# H0DR9_Backend.net
KiCad netlist of a schematic drawn in Altium Designer
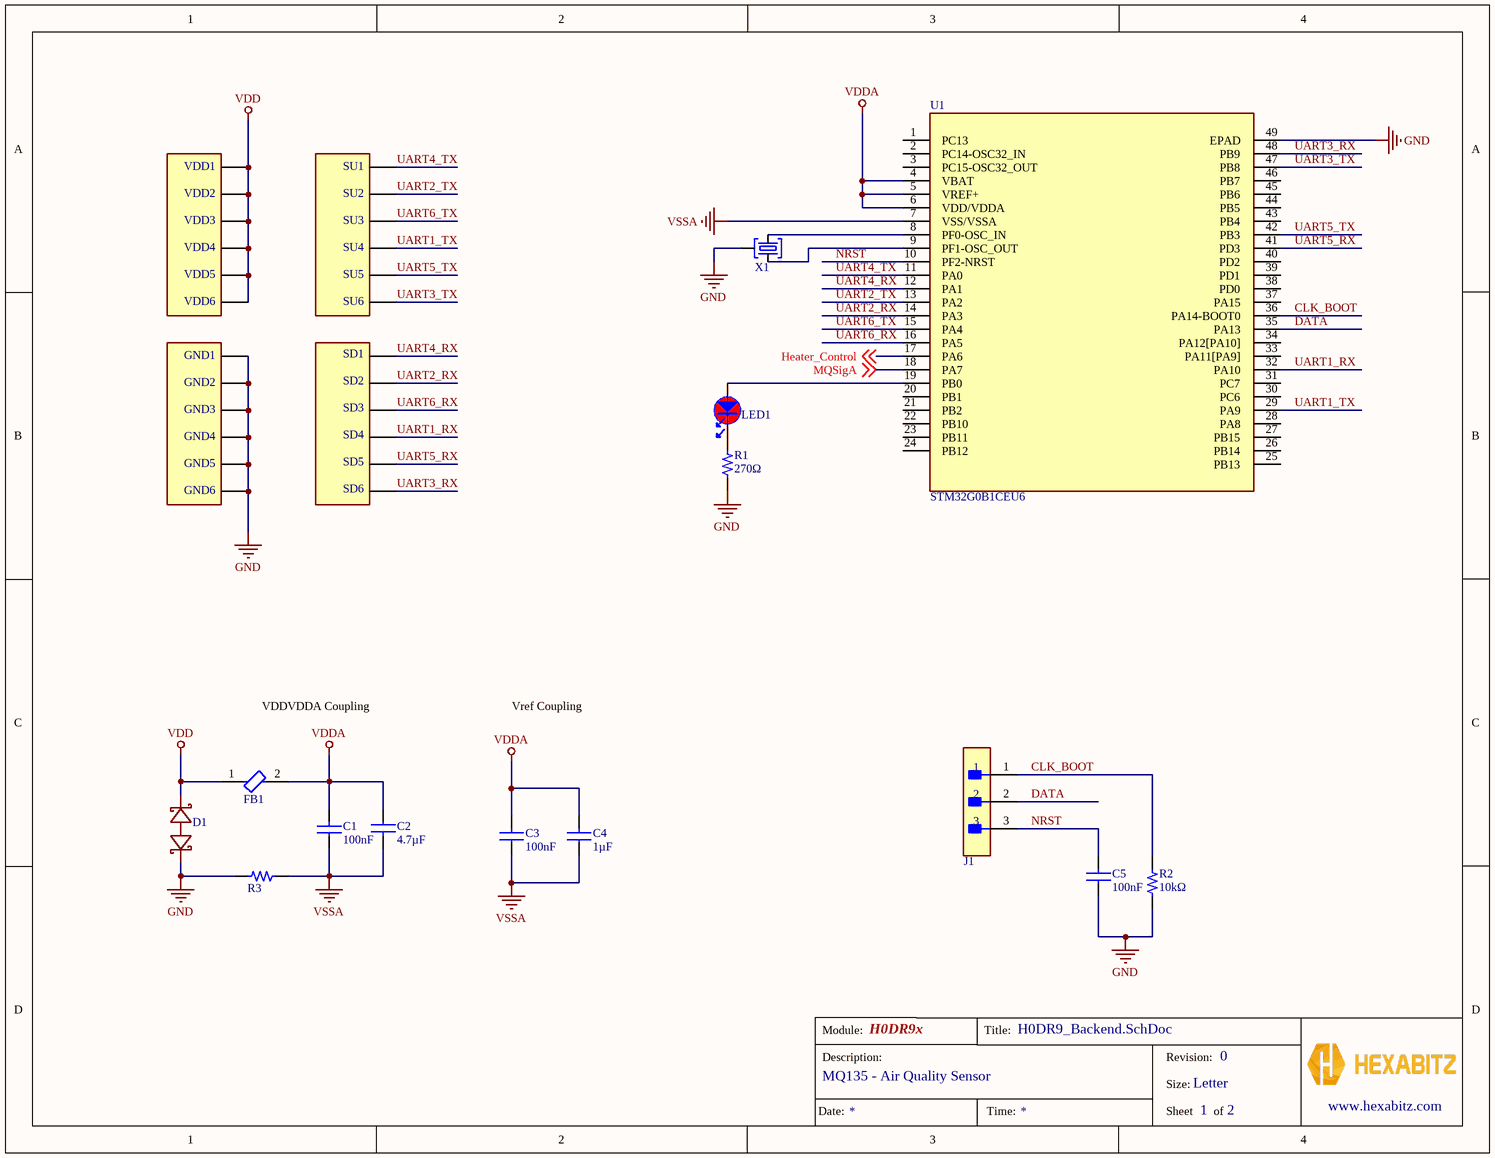
[diagram p0: H0DR9_Backend.SchDoc]

(export (version "E")
  (design (tool "Eeschema 10.0.6"))
  (components
    (comp (ref "C1")
      (value "100nF")
      (footprint "C0603")
      (fields
        (field (name "MANUFACTURER") "Samsung Electro-Mechanics")
        (field (name "MANUFACTURER PART NUMBER") "CL10B104KA8NNNC")
        (field (name "TOLERANCE") "10%")
      )
      (libsource (lib "Hexabitz Altium Library") (part "generic Capacitor"))
    )
    (comp (ref "C2")
      (value "4.7µF")
      (footprint "C0805")
      (fields
        (field (name "MANUFACTURER") "Samsung Electro-Mechanics")
        (field (name "MANUFACTURER PART NUMBER") "CL21X475KAQNNNE")
        (field (name "TOLERANCE") "10%")
      )
      (libsource (lib "Hexabitz Altium Library") (part "generic Capacitor"))
    )
    (comp (ref "C3")
      (value "100nF")
      (footprint "C0603")
      (fields
        (field (name "MANUFACTURER") "Samsung Electro-Mechanics")
        (field (name "MANUFACTURER PART NUMBER") "CL10B104KA8NNNC")
        (field (name "TOLERANCE") "10%")
      )
      (libsource (lib "Hexabitz Altium Library") (part "generic Capacitor"))
    )
    (comp (ref "C4")
      (value "1µF")
      (footprint "C0805")
      (description "Ceramic Capacitor, Ceramic, 16V, 10% +Tol, 10% -Tol, X7R, 15% TC, 1uF, Surface Mount, 0805")
      (fields
        (field (name "MANUFACTURER") "Yageo Group")
        (field (name "MANUFACTURER PART NUMBER") "CC0805KKX7R7BB105")
      )
      (libsource (lib "Hexabitz Altium Library") (part "generic Capacitor"))
    )
    (comp (ref "C5")
      (value "100nF")
      (footprint "C0603")
      (fields
        (field (name "MANUFACTURER") "Samsung Electro-Mechanics")
        (field (name "MANUFACTURER PART NUMBER") "CL10B104KA8NNNC")
        (field (name "TOLERANCE") "10%")
      )
      (libsource (lib "Hexabitz Altium Library") (part "generic Capacitor"))
    )
    (comp (ref "D1")
      (value "CDSOD323-T03SC")
      (footprint "SOD2513X114N")
      (description "A 3V, 350W, bi-directional, standard capacitance, SOD323 pkg TVS Diode ¦ Bourns CDSOD323-T03SC")
      (fields (field (name "MANUFACTURER") "Bourns"))
      (libsource (lib "Hexabitz Altium Library") (part "CDSOD323-T03SC"))
    )
    (comp (ref "FB1")
      (value "MMZ1608Y300B")
      (footprint "FP-MMZ1608-0_8-MFG")
      (description "Ferrite Beads 0603 30ohms 1500mA Signal Line AEC-Q200")
      (fields
        (field (name "MANUFACTURER") "TDK")
        (field (name "MANUFACTURER PART NUMBER") "MMZ1608Y300BTD25")
      )
      (libsource (lib "Hexabitz Altium Library") (part "MMZ1608Y300B"))
    )
    (comp (ref "GND1")
      (value "HEXABIT_UART_PORT")
      (footprint "HEXABIT_POWER_PORT_D")
      (libsource (lib "hexabitz_connectors.Library") (part "HEXABIT_POWER_PORT_D"))
    )
    (comp (ref "GND2")
      (value "HEXABIT_UART_PORT")
      (footprint "HEXABIT_POWER_PORT_D")
      (libsource (lib "hexabitz_connectors.Library") (part "HEXABIT_POWER_PORT_D"))
    )
    (comp (ref "GND3")
      (value "HEXABIT_UART_PORT")
      (footprint "HEXABIT_POWER_PORT_D")
      (libsource (lib "hexabitz_connectors.Library") (part "HEXABIT_POWER_PORT_D"))
    )
    (comp (ref "GND4")
      (value "HEXABIT_UART_PORT")
      (footprint "HEXABIT_POWER_PORT_D")
      (libsource (lib "hexabitz_connectors.Library") (part "HEXABIT_POWER_PORT_D"))
    )
    (comp (ref "GND5")
      (value "HEXABIT_UART_PORT")
      (footprint "HEXABIT_POWER_PORT_D")
      (libsource (lib "hexabitz_connectors.Library") (part "HEXABIT_POWER_PORT_D"))
    )
    (comp (ref "GND6")
      (value "HEXABIT_UART_PORT")
      (footprint "HEXABIT_POWER_PORT_D")
      (libsource (lib "hexabitz_connectors.Library") (part "HEXABIT_POWER_PORT_D"))
    )
    (comp (ref "J1")
      (value "TSW-103-14-G-S")
      (footprint "FP-TSW-103-14-G-S-MFG")
      (description "CONN HEADER VERT 3POS 2.54MM")
      (libsource (lib "Altium Content Vault") (part "cd3439d6ef35ae5d9b27ec4fdd3e828"))
    )
    (comp (ref "LED1")
      (value "VLMS1300-GS08")
      (footprint "FP-6_541-5092_01-4-MFG")
      (description "LED Uni-Color Super Red 639nm 2-Pin Chip 0603(1608Metric) T/R")
      (fields (field (name "MANUFACTURER") "Vishay Semiconductors"))
      (libsource (lib "Hexabitz Altium Library") (part "VLMS1300-GS08"))
    )
    (comp (ref "R1")
      (value "270Ω")
      (footprint "R0603")
      (description "Res Thick Film 0603 270 Ohm 5% 0.1W(1/10W) ±200ppm/C Pad SMD Automotive T/R")
      (fields
        (field (name "MANUFACTURER") "Panasonic")
        (field (name "MANUFACTURER PART NUMBER") "ERJ-3GEYJ271V")
      )
      (libsource (lib "") (part "generic Resistor_1"))
    )
    (comp (ref "R2")
      (value "10kΩ")
      (footprint "R0603")
      (description "100mW Thick Film Resistors ±100ppm/℃ ±1% 10kΩ 0603 Chip Resistor - Surface Mount ROHS")
      (fields
        (field (name "MANUFACTURER") "Yageo Group")
        (field (name "MANUFACTURER PART NUMBER") "RC0603FR-0710KL")
      )
      (libsource (lib "Hexabitz Altium Library") (part "generic Resistor"))
    )
    (comp (ref "R3")
      (value "Manufacturer Part Number")
      (footprint "R0603")
      (libsource (lib "") (part "generic Resistor_2"))
    )
    (comp (ref "SD1")
      (value "HEXABIT_UART_PORT")
      (footprint "HEXABIT_UART_PORT_D")
      (libsource (lib "hexabitz_connectors.Library") (part "HEXABIT_UART_PORT_D"))
    )
    (comp (ref "SD2")
      (value "HEXABIT_UART_PORT")
      (footprint "HEXABIT_UART_PORT_D")
      (libsource (lib "hexabitz_connectors.Library") (part "HEXABIT_UART_PORT_D"))
    )
    (comp (ref "SD3")
      (value "HEXABIT_UART_PORT")
      (footprint "HEXABIT_UART_PORT_D")
      (libsource (lib "hexabitz_connectors.Library") (part "HEXABIT_UART_PORT_D"))
    )
    (comp (ref "SD4")
      (value "HEXABIT_UART_PORT")
      (footprint "HEXABIT_UART_PORT_D")
      (libsource (lib "hexabitz_connectors.Library") (part "HEXABIT_UART_PORT_D"))
    )
    (comp (ref "SD5")
      (value "HEXABIT_UART_PORT")
      (footprint "HEXABIT_UART_PORT_D")
      (libsource (lib "hexabitz_connectors.Library") (part "HEXABIT_UART_PORT_D"))
    )
    (comp (ref "SD6")
      (value "HEXABIT_UART_PORT")
      (footprint "HEXABIT_UART_PORT_D")
      (libsource (lib "hexabitz_connectors.Library") (part "HEXABIT_UART_PORT_D"))
    )
    (comp (ref "SU1")
      (value "HEXABIT_UART_PORT")
      (footprint "HEXABIT_UART_PORT_U")
      (libsource (lib "hexabitz_connectors.Library") (part "HEXABIT_UART_PORT_U"))
    )
    (comp (ref "SU2")
      (value "HEXABIT_UART_PORT")
      (footprint "HEXABIT_UART_PORT_U")
      (libsource (lib "hexabitz_connectors.Library") (part "HEXABIT_UART_PORT_U"))
    )
    (comp (ref "SU3")
      (value "HEXABIT_UART_PORT")
      (footprint "HEXABIT_UART_PORT_U")
      (libsource (lib "hexabitz_connectors.Library") (part "HEXABIT_UART_PORT_U"))
    )
    (comp (ref "SU4")
      (value "HEXABIT_UART_PORT")
      (footprint "HEXABIT_UART_PORT_U")
      (libsource (lib "hexabitz_connectors.Library") (part "HEXABIT_UART_PORT_U"))
    )
    (comp (ref "SU5")
      (value "HEXABIT_UART_PORT")
      (footprint "HEXABIT_UART_PORT_U")
      (libsource (lib "hexabitz_connectors.Library") (part "HEXABIT_UART_PORT_U"))
    )
    (comp (ref "SU6")
      (value "HEXABIT_UART_PORT")
      (footprint "HEXABIT_UART_PORT_U")
      (libsource (lib "hexabitz_connectors.Library") (part "HEXABIT_UART_PORT_U"))
    )
    (comp (ref "U1")
      (value "STM32G0B1CEU6")
      (footprint "QFN50P700X700X65-49N-D")
      (description "MCU 32-bit ARM Cortex M0+ RISC 512KB Flash 1.8V/2.5V/3.3V 48-Pin UFQFPN EP Tray")
      (fields
        (field (name "MANUFACTURER") "STMicroelectronics")
        (field (name "MANUFACTURER PART NUMBER") "STM32G0B1CEU6")
      )
      (libsource (lib "Hexabitz Altium Library") (part "STM32G0B1CEU6"))
    )
    (comp (ref "VDD1")
      (value "HEXABIT_UART_PORT")
      (footprint "HEXABIT_POWER_PORT_U")
      (libsource (lib "hexabitz_connectors.Library") (part "HEXABIT_POWER_PORT_U"))
    )
    (comp (ref "VDD2")
      (value "HEXABIT_UART_PORT")
      (footprint "HEXABIT_POWER_PORT_U")
      (libsource (lib "hexabitz_connectors.Library") (part "HEXABIT_POWER_PORT_U"))
    )
    (comp (ref "VDD3")
      (value "HEXABIT_UART_PORT")
      (footprint "HEXABIT_POWER_PORT_U")
      (libsource (lib "hexabitz_connectors.Library") (part "HEXABIT_POWER_PORT_U"))
    )
    (comp (ref "VDD4")
      (value "HEXABIT_UART_PORT")
      (footprint "HEXABIT_POWER_PORT_U")
      (libsource (lib "hexabitz_connectors.Library") (part "HEXABIT_POWER_PORT_U"))
    )
    (comp (ref "VDD5")
      (value "HEXABIT_UART_PORT")
      (footprint "HEXABIT_POWER_PORT_U")
      (libsource (lib "hexabitz_connectors.Library") (part "HEXABIT_POWER_PORT_U"))
    )
    (comp (ref "VDD6")
      (value "HEXABIT_UART_PORT")
      (footprint "HEXABIT_POWER_PORT_U")
      (libsource (lib "hexabitz_connectors.Library") (part "HEXABIT_POWER_PORT_U"))
    )
    (comp (ref "X1")
      (value "CSTCE8M00G52Z-R0")
      (footprint "XTALL_CSTCE8M00G52")
      (description "Ceramic Resonator 8MHz ±0.5% (Tol) ±0.2% (Stability) 10pF 40Ohm 3-Pin CSMD T/R")
      (fields (field (name "MANUFACTURER") "Murata") (field (name "TOLERANCE") "0.5%"))
      (libsource (lib "Hexabitz Altium Library") (part "CSTCE8M00G52Z-R0"))
    )
  )
  (nets
    (net (code "1") (name "/CLK_BOOT") (class "Default")
      (node (ref "J1") (pin "1") (pinfunction "1_1") (pintype "passive"))
      (node (ref "R2") (pin "1") (pinfunction "1_1") (pintype "passive"))
      (node (ref "U1") (pin "36") (pinfunction "PA14-BOOT0_36") (pintype "passive"))
    )
    (net (code "2") (name "/DATA") (class "Default")
      (node (ref "J1") (pin "2") (pinfunction "2_2") (pintype "passive"))
      (node (ref "U1") (pin "35") (pinfunction "PA13_35") (pintype "passive"))
    )
    (net (code "3") (name "/NRST") (class "Default")
      (node (ref "C5") (pin "2") (pinfunction "2_2") (pintype "passive"))
      (node (ref "J1") (pin "3") (pinfunction "3_3") (pintype "passive"))
      (node (ref "U1") (pin "10") (pinfunction "PF2-NRST_10") (pintype "passive"))
    )
    (net (code "4") (name "/UART1_RX") (class "Default")
      (node (ref "SD4") (pin "UART_D") (pinfunction "UART_D_UART_D") (pintype "passive"))
      (node (ref "U1") (pin "32") (pinfunction "PA10_32") (pintype "passive"))
    )
    (net (code "5") (name "/UART1_TX") (class "Default")
      (node (ref "SU4") (pin "UART_U") (pinfunction "UART_U_UART_U") (pintype "passive"))
      (node (ref "U1") (pin "29") (pinfunction "PA9_29") (pintype "passive"))
    )
    (net (code "6") (name "/UART2_RX") (class "Default")
      (node (ref "SD2") (pin "UART_D") (pinfunction "UART_D_UART_D") (pintype "passive"))
      (node (ref "U1") (pin "14") (pinfunction "PA3_14") (pintype "passive"))
    )
    (net (code "7") (name "/UART2_TX") (class "Default")
      (node (ref "SU2") (pin "UART_U") (pinfunction "UART_U_UART_U") (pintype "passive"))
      (node (ref "U1") (pin "13") (pinfunction "PA2_13") (pintype "passive"))
    )
    (net (code "8") (name "/UART3_RX") (class "Default")
      (node (ref "SD6") (pin "UART_D") (pinfunction "UART_D_UART_D") (pintype "passive"))
      (node (ref "U1") (pin "48") (pinfunction "PB9_48") (pintype "passive"))
    )
    (net (code "9") (name "/UART3_TX") (class "Default")
      (node (ref "SU6") (pin "UART_U") (pinfunction "UART_U_UART_U") (pintype "passive"))
      (node (ref "U1") (pin "47") (pinfunction "PB8_47") (pintype "passive"))
    )
    (net (code "10") (name "/UART4_RX") (class "Default")
      (node (ref "SD1") (pin "UART_D") (pinfunction "UART_D_UART_D") (pintype "passive"))
      (node (ref "U1") (pin "12") (pinfunction "PA1_12") (pintype "passive"))
    )
    (net (code "11") (name "/UART4_TX") (class "Default")
      (node (ref "SU1") (pin "UART_U") (pinfunction "UART_U_UART_U") (pintype "passive"))
      (node (ref "U1") (pin "11") (pinfunction "PA0_11") (pintype "passive"))
    )
    (net (code "12") (name "/UART5_RX") (class "Default")
      (node (ref "SD5") (pin "UART_D") (pinfunction "UART_D_UART_D") (pintype "passive"))
      (node (ref "U1") (pin "41") (pinfunction "PD3_41") (pintype "passive"))
    )
    (net (code "13") (name "/UART5_TX") (class "Default")
      (node (ref "SU5") (pin "UART_U") (pinfunction "UART_U_UART_U") (pintype "passive"))
      (node (ref "U1") (pin "42") (pinfunction "PB3_42") (pintype "passive"))
    )
    (net (code "14") (name "/UART6_RX") (class "Default")
      (node (ref "SD3") (pin "UART_D") (pinfunction "UART_D_UART_D") (pintype "passive"))
      (node (ref "U1") (pin "16") (pinfunction "PA5_16") (pintype "passive"))
    )
    (net (code "15") (name "/UART6_TX") (class "Default")
      (node (ref "SU3") (pin "UART_U") (pinfunction "UART_U_UART_U") (pintype "passive"))
      (node (ref "U1") (pin "15") (pinfunction "PA4_15") (pintype "passive"))
    )
    (net (code "16") (name "GND") (class "Default")
      (node (ref "C5") (pin "1") (pinfunction "1_1") (pintype "passive"))
      (node (ref "D1") (pin "1") (pinfunction "A_1") (pintype "passive"))
      (node (ref "GND1") (pin "Pwr_D") (pinfunction "Pwr_D_Pwr_D") (pintype "passive"))
      (node (ref "GND2") (pin "Pwr_D") (pinfunction "Pwr_D_Pwr_D") (pintype "passive"))
      (node (ref "GND3") (pin "Pwr_D") (pinfunction "Pwr_D_Pwr_D") (pintype "passive"))
      (node (ref "GND4") (pin "Pwr_D") (pinfunction "Pwr_D_Pwr_D") (pintype "passive"))
      (node (ref "GND5") (pin "Pwr_D") (pinfunction "Pwr_D_Pwr_D") (pintype "passive"))
      (node (ref "GND6") (pin "Pwr_D") (pinfunction "Pwr_D_Pwr_D") (pintype "passive"))
      (node (ref "R1") (pin "1") (pinfunction "1_1") (pintype "passive"))
      (node (ref "R2") (pin "2") (pinfunction "2_2") (pintype "passive"))
      (node (ref "R3") (pin "1") (pinfunction "1_1") (pintype "passive"))
      (node (ref "U1") (pin "49") (pinfunction "EPAD_49") (pintype "passive"))
      (node (ref "X1") (pin "P$2") (pinfunction "2_P$2") (pintype "passive"))
    )
    (net (code "17") (name "Heater_Control") (class "Default")
      (node (ref "U1") (pin "17") (pinfunction "PA6_17") (pintype "passive"))
    )
    (net (code "18") (name "MQSigA") (class "Default")
      (node (ref "U1") (pin "18") (pinfunction "PA7_18") (pintype "passive"))
    )
    (net (code "19") (name "Net-(LED1-Pad1)") (class "Default")
      (node (ref "LED1") (pin "1") (pintype "passive"))
      (node (ref "R1") (pin "2") (pinfunction "2_2") (pintype "passive"))
    )
    (net (code "20") (name "Net-(U1-PB0)") (class "Default")
      (node (ref "LED1") (pin "2") (pintype "passive"))
      (node (ref "U1") (pin "19") (pinfunction "PB0_19") (pintype "passive"))
    )
    (net (code "21") (name "Net-(U1-PF0-OSC_IN)") (class "Default")
      (node (ref "U1") (pin "8") (pinfunction "PF0-OSC_IN_8") (pintype "passive"))
      (node (ref "X1") (pin "P$3") (pinfunction "3_P$3") (pintype "passive"))
    )
    (net (code "22") (name "Net-(U1-PF1-OSC_OUT)") (class "Default")
      (node (ref "U1") (pin "9") (pinfunction "PF1-OSC_OUT_9") (pintype "passive"))
      (node (ref "X1") (pin "P$1") (pinfunction "1_P$1") (pintype "passive"))
    )
    (net (code "23") (name "VDD") (class "Default")
      (node (ref "D1") (pin "2") (pinfunction "C_2") (pintype "passive"))
      (node (ref "FB1") (pin "1") (pinfunction "1_1") (pintype "passive"))
      (node (ref "VDD1") (pin "Pwr_U") (pinfunction "Pwr_U_Pwr_U") (pintype "passive"))
      (node (ref "VDD2") (pin "Pwr_U") (pinfunction "Pwr_U_Pwr_U") (pintype "passive"))
      (node (ref "VDD3") (pin "Pwr_U") (pinfunction "Pwr_U_Pwr_U") (pintype "passive"))
      (node (ref "VDD4") (pin "Pwr_U") (pinfunction "Pwr_U_Pwr_U") (pintype "passive"))
      (node (ref "VDD5") (pin "Pwr_U") (pinfunction "Pwr_U_Pwr_U") (pintype "passive"))
      (node (ref "VDD6") (pin "Pwr_U") (pinfunction "Pwr_U_Pwr_U") (pintype "passive"))
    )
    (net (code "24") (name "VDDA") (class "Default")
      (node (ref "C1") (pin "2") (pinfunction "2_2") (pintype "passive"))
      (node (ref "C2") (pin "1") (pinfunction "1_1") (pintype "passive"))
      (node (ref "C3") (pin "2") (pinfunction "2_2") (pintype "passive"))
      (node (ref "C4") (pin "2") (pinfunction "2_2") (pintype "passive"))
      (node (ref "FB1") (pin "2") (pinfunction "2_2") (pintype "passive"))
      (node (ref "U1") (pin "4") (pinfunction "VBAT_4") (pintype "passive"))
      (node (ref "U1") (pin "5") (pinfunction "VREF+_5") (pintype "passive"))
      (node (ref "U1") (pin "6") (pinfunction "VDD/VDDA_6") (pintype "passive"))
    )
    (net (code "25") (name "VSSA") (class "Default")
      (node (ref "C1") (pin "1") (pinfunction "1_1") (pintype "passive"))
      (node (ref "C2") (pin "2") (pinfunction "2_2") (pintype "passive"))
      (node (ref "C3") (pin "1") (pinfunction "1_1") (pintype "passive"))
      (node (ref "C4") (pin "1") (pinfunction "1_1") (pintype "passive"))
      (node (ref "R3") (pin "2") (pinfunction "2_2") (pintype "passive"))
      (node (ref "U1") (pin "7") (pinfunction "VSS/VSSA_7") (pintype "passive"))
    )
    (net (code "26") (name "unconnected-(U1-PA8-Pad28)") (class "Default")
      (node (ref "U1") (pin "28") (pinfunction "PA8_28") (pintype "passive"))
    )
    (net (code "27") (name "unconnected-(U1-PA11[PA9]-Pad33)") (class "Default")
      (node (ref "U1") (pin "33") (pinfunction "PA11[PA9]_33") (pintype "passive"))
    )
    (net (code "28") (name "unconnected-(U1-PA12[PA10]-Pad34)") (class "Default")
      (node (ref "U1") (pin "34") (pinfunction "PA12[PA10]_34") (pintype "passive"))
    )
    (net (code "29") (name "unconnected-(U1-PA15-Pad37)") (class "Default")
      (node (ref "U1") (pin "37") (pinfunction "PA15_37") (pintype "passive"))
    )
    (net (code "30") (name "unconnected-(U1-PB1-Pad20)") (class "Default")
      (node (ref "U1") (pin "20") (pinfunction "PB1_20") (pintype "passive"))
    )
    (net (code "31") (name "unconnected-(U1-PB2-Pad21)") (class "Default")
      (node (ref "U1") (pin "21") (pinfunction "PB2_21") (pintype "passive"))
    )
    (net (code "32") (name "unconnected-(U1-PB4-Pad43)") (class "Default")
      (node (ref "U1") (pin "43") (pinfunction "PB4_43") (pintype "passive"))
    )
    (net (code "33") (name "unconnected-(U1-PB5-Pad44)") (class "Default")
      (node (ref "U1") (pin "44") (pinfunction "PB5_44") (pintype "passive"))
    )
    (net (code "34") (name "unconnected-(U1-PB6-Pad45)") (class "Default")
      (node (ref "U1") (pin "45") (pinfunction "PB6_45") (pintype "passive"))
    )
    (net (code "35") (name "unconnected-(U1-PB7-Pad46)") (class "Default")
      (node (ref "U1") (pin "46") (pinfunction "PB7_46") (pintype "passive"))
    )
    (net (code "36") (name "unconnected-(U1-PB10-Pad22)") (class "Default")
      (node (ref "U1") (pin "22") (pinfunction "PB10_22") (pintype "passive"))
    )
    (net (code "37") (name "unconnected-(U1-PB11-Pad23)") (class "Default")
      (node (ref "U1") (pin "23") (pinfunction "PB11_23") (pintype "passive"))
    )
    (net (code "38") (name "unconnected-(U1-PB12-Pad24)") (class "Default")
      (node (ref "U1") (pin "24") (pinfunction "PB12_24") (pintype "passive"))
    )
    (net (code "39") (name "unconnected-(U1-PB13-Pad25)") (class "Default")
      (node (ref "U1") (pin "25") (pinfunction "PB13_25") (pintype "passive"))
    )
    (net (code "40") (name "unconnected-(U1-PB14-Pad26)") (class "Default")
      (node (ref "U1") (pin "26") (pinfunction "PB14_26") (pintype "passive"))
    )
    (net (code "41") (name "unconnected-(U1-PB15-Pad27)") (class "Default")
      (node (ref "U1") (pin "27") (pinfunction "PB15_27") (pintype "passive"))
    )
    (net (code "42") (name "unconnected-(U1-PC6-Pad30)") (class "Default")
      (node (ref "U1") (pin "30") (pinfunction "PC6_30") (pintype "passive"))
    )
    (net (code "43") (name "unconnected-(U1-PC7-Pad31)") (class "Default")
      (node (ref "U1") (pin "31") (pinfunction "PC7_31") (pintype "passive"))
    )
    (net (code "44") (name "unconnected-(U1-PC13-Pad1)") (class "Default")
      (node (ref "U1") (pin "1") (pinfunction "PC13_1") (pintype "passive"))
    )
    (net (code "45") (name "unconnected-(U1-PC14-OSC32_IN-Pad2)") (class "Default")
      (node (ref "U1") (pin "2") (pinfunction "PC14-OSC32_IN_2") (pintype "passive"))
    )
    (net (code "46") (name "unconnected-(U1-PC15-OSC32_OUT-Pad3)") (class "Default")
      (node (ref "U1") (pin "3") (pinfunction "PC15-OSC32_OUT_3") (pintype "passive"))
    )
    (net (code "47") (name "unconnected-(U1-PD0-Pad38)") (class "Default")
      (node (ref "U1") (pin "38") (pinfunction "PD0_38") (pintype "passive"))
    )
    (net (code "48") (name "unconnected-(U1-PD1-Pad39)") (class "Default")
      (node (ref "U1") (pin "39") (pinfunction "PD1_39") (pintype "passive"))
    )
    (net (code "49") (name "unconnected-(U1-PD2-Pad40)") (class "Default")
      (node (ref "U1") (pin "40") (pinfunction "PD2_40") (pintype "passive"))
    )
  )
)
